# mosca.net
KiCad netlist of a schematic drawn in EAGLE
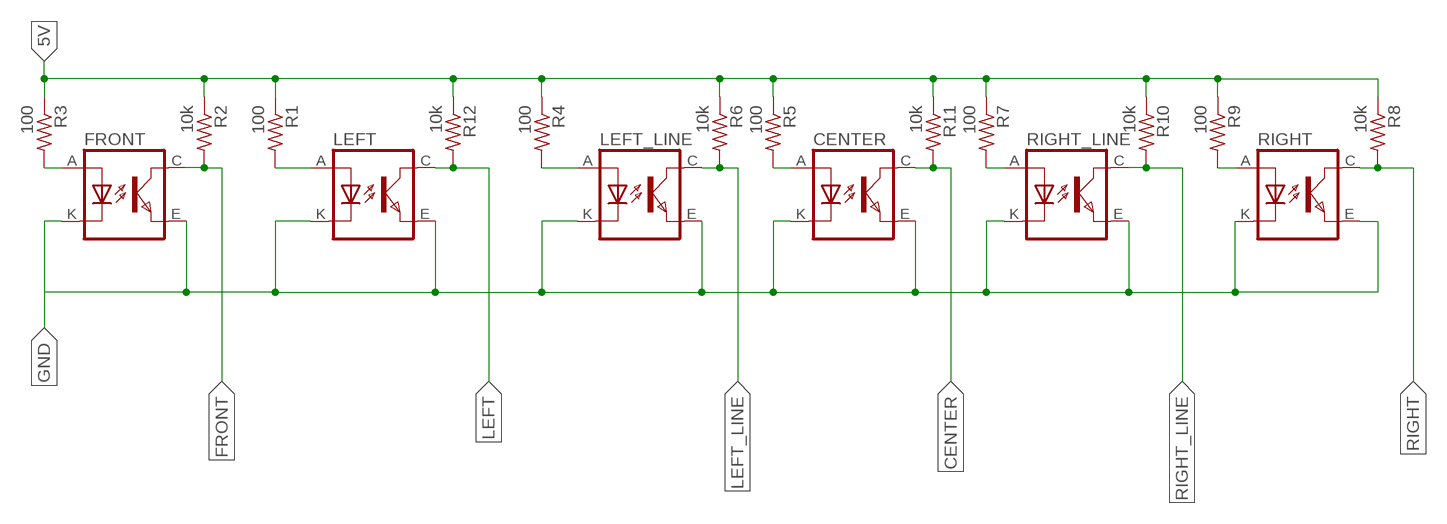
[diagram p0: schematic, sheet 1]

(export (version "E")
  (design (tool "Eeschema 10.0.6"))
  (components
    (comp (ref "CENTER")
      (value "TCRT5000")
      (footprint "eagle-import:TCRT5000")
      (libsource (lib "eagle-import") (part "TCRT5000"))
    )
    (comp (ref "FRONT")
      (value "TCRT5000")
      (footprint "eagle-import:TCRT5000")
      (libsource (lib "eagle-import") (part "TCRT5000"))
    )
    (comp (ref "LEFT")
      (value "TCRT5000")
      (footprint "eagle-import:TCRT5000")
      (libsource (lib "eagle-import") (part "TCRT5000"))
    )
    (comp (ref "LEFT_LINE")
      (value "TCRT5000")
      (footprint "eagle-import:TCRT5000")
      (libsource (lib "eagle-import") (part "TCRT5000"))
    )
    (comp (ref "R1")
      (value "100")
      (footprint "eagle-import:0204_7")
      (libsource (lib "eagle-import") (part "R-US_0204/7"))
    )
    (comp (ref "R2")
      (value "10k")
      (footprint "eagle-import:0204_7")
      (libsource (lib "eagle-import") (part "R-US_0204/7"))
    )
    (comp (ref "R3")
      (value "100")
      (footprint "eagle-import:0204_7")
      (libsource (lib "eagle-import") (part "R-US_0204/7"))
    )
    (comp (ref "R4")
      (value "100")
      (footprint "eagle-import:0204_7")
      (libsource (lib "eagle-import") (part "R-US_0204/7"))
    )
    (comp (ref "R5")
      (value "100")
      (footprint "eagle-import:0204_7")
      (libsource (lib "eagle-import") (part "R-US_0204/7"))
    )
    (comp (ref "R6")
      (value "10k")
      (footprint "eagle-import:0204_7")
      (libsource (lib "eagle-import") (part "R-US_0204/7"))
    )
    (comp (ref "R7")
      (value "100")
      (footprint "eagle-import:0204_7")
      (libsource (lib "eagle-import") (part "R-US_0204/7"))
    )
    (comp (ref "R8")
      (value "10k")
      (footprint "eagle-import:0204_7")
      (libsource (lib "eagle-import") (part "R-US_0204/7"))
    )
    (comp (ref "R9")
      (value "100")
      (footprint "eagle-import:0204_7")
      (libsource (lib "eagle-import") (part "R-US_0204/7"))
    )
    (comp (ref "R10")
      (value "10k")
      (footprint "eagle-import:0204_7")
      (libsource (lib "eagle-import") (part "R-US_0204/7"))
    )
    (comp (ref "R11")
      (value "10k")
      (footprint "eagle-import:0204_7")
      (libsource (lib "eagle-import") (part "R-US_0204/7"))
    )
    (comp (ref "R12")
      (value "10k")
      (footprint "eagle-import:0204_7")
      (libsource (lib "eagle-import") (part "R-US_0204/7"))
    )
    (comp (ref "RIGHT")
      (value "TCRT5000")
      (footprint "eagle-import:TCRT5000")
      (libsource (lib "eagle-import") (part "TCRT5000"))
    )
    (comp (ref "RIGHT_LINE")
      (value "TCRT5000")
      (footprint "eagle-import:TCRT5000")
      (libsource (lib "eagle-import") (part "TCRT5000"))
    )
  )
  (nets
    (net (code "1") (name "5V") (class "Default")
      (node (ref "R1") (pin "1") (pinfunction "1_1") (pintype "passive"))
      (node (ref "R10") (pin "1") (pinfunction "1_1") (pintype "passive"))
      (node (ref "R11") (pin "1") (pinfunction "1_1") (pintype "passive"))
      (node (ref "R12") (pin "1") (pinfunction "1_1") (pintype "passive"))
      (node (ref "R2") (pin "1") (pinfunction "1_1") (pintype "passive"))
      (node (ref "R3") (pin "1") (pinfunction "1_1") (pintype "passive"))
      (node (ref "R4") (pin "1") (pinfunction "1_1") (pintype "passive"))
      (node (ref "R5") (pin "1") (pinfunction "1_1") (pintype "passive"))
      (node (ref "R6") (pin "1") (pinfunction "1_1") (pintype "passive"))
      (node (ref "R7") (pin "1") (pinfunction "1_1") (pintype "passive"))
      (node (ref "R8") (pin "1") (pinfunction "1_1") (pintype "passive"))
      (node (ref "R9") (pin "1") (pinfunction "1_1") (pintype "passive"))
    )
    (net (code "2") (name "CENTER") (class "Default")
      (node (ref "CENTER") (pin "C") (pinfunction "COLLECTOR_C") (pintype "passive"))
      (node (ref "R11") (pin "2") (pinfunction "2_2") (pintype "passive"))
    )
    (net (code "3") (name "FRONT") (class "Default")
      (node (ref "FRONT") (pin "C") (pinfunction "COLLECTOR_C") (pintype "passive"))
      (node (ref "R2") (pin "2") (pinfunction "2_2") (pintype "passive"))
    )
    (net (code "4") (name "GND") (class "Default")
      (node (ref "CENTER") (pin "E") (pinfunction "EMITTER_E") (pintype "passive"))
      (node (ref "CENTER") (pin "K") (pinfunction "CATHODE_K") (pintype "passive"))
      (node (ref "FRONT") (pin "E") (pinfunction "EMITTER_E") (pintype "passive"))
      (node (ref "FRONT") (pin "K") (pinfunction "CATHODE_K") (pintype "passive"))
      (node (ref "LEFT") (pin "E") (pinfunction "EMITTER_E") (pintype "passive"))
      (node (ref "LEFT") (pin "K") (pinfunction "CATHODE_K") (pintype "passive"))
      (node (ref "LEFT_LINE") (pin "E") (pinfunction "EMITTER_E") (pintype "passive"))
      (node (ref "LEFT_LINE") (pin "K") (pinfunction "CATHODE_K") (pintype "passive"))
      (node (ref "RIGHT") (pin "E") (pinfunction "EMITTER_E") (pintype "passive"))
      (node (ref "RIGHT") (pin "K") (pinfunction "CATHODE_K") (pintype "passive"))
      (node (ref "RIGHT_LINE") (pin "E") (pinfunction "EMITTER_E") (pintype "passive"))
      (node (ref "RIGHT_LINE") (pin "K") (pinfunction "CATHODE_K") (pintype "passive"))
    )
    (net (code "5") (name "LEFT") (class "Default")
      (node (ref "LEFT") (pin "C") (pinfunction "COLLECTOR_C") (pintype "passive"))
      (node (ref "R12") (pin "2") (pinfunction "2_2") (pintype "passive"))
    )
    (net (code "6") (name "LEFT_LINE") (class "Default")
      (node (ref "LEFT_LINE") (pin "C") (pinfunction "COLLECTOR_C") (pintype "passive"))
      (node (ref "R6") (pin "2") (pinfunction "2_2") (pintype "passive"))
    )
    (net (code "7") (name "Net-(CENTER-ANODE)") (class "Default")
      (node (ref "CENTER") (pin "A") (pinfunction "ANODE_A") (pintype "passive"))
      (node (ref "R5") (pin "2") (pinfunction "2_2") (pintype "passive"))
    )
    (net (code "8") (name "Net-(FRONT-ANODE)") (class "Default")
      (node (ref "FRONT") (pin "A") (pinfunction "ANODE_A") (pintype "passive"))
      (node (ref "R3") (pin "2") (pinfunction "2_2") (pintype "passive"))
    )
    (net (code "9") (name "Net-(LEFT-ANODE)") (class "Default")
      (node (ref "LEFT") (pin "A") (pinfunction "ANODE_A") (pintype "passive"))
      (node (ref "R1") (pin "2") (pinfunction "2_2") (pintype "passive"))
    )
    (net (code "10") (name "Net-(LEFT_LINE-ANODE)") (class "Default")
      (node (ref "LEFT_LINE") (pin "A") (pinfunction "ANODE_A") (pintype "passive"))
      (node (ref "R4") (pin "2") (pinfunction "2_2") (pintype "passive"))
    )
    (net (code "11") (name "Net-(RIGHT-ANODE)") (class "Default")
      (node (ref "R9") (pin "2") (pinfunction "2_2") (pintype "passive"))
      (node (ref "RIGHT") (pin "A") (pinfunction "ANODE_A") (pintype "passive"))
    )
    (net (code "12") (name "Net-(RIGHT_LINE-ANODE)") (class "Default")
      (node (ref "R7") (pin "2") (pinfunction "2_2") (pintype "passive"))
      (node (ref "RIGHT_LINE") (pin "A") (pinfunction "ANODE_A") (pintype "passive"))
    )
    (net (code "13") (name "RIGHT") (class "Default")
      (node (ref "R8") (pin "2") (pinfunction "2_2") (pintype "passive"))
      (node (ref "RIGHT") (pin "C") (pinfunction "COLLECTOR_C") (pintype "passive"))
    )
    (net (code "14") (name "RIGHT_LINE") (class "Default")
      (node (ref "R10") (pin "2") (pinfunction "2_2") (pintype "passive"))
      (node (ref "RIGHT_LINE") (pin "C") (pinfunction "COLLECTOR_C") (pintype "passive"))
    )
  )
)
